# kossr.net
KiCad netlist of a schematic drawn in EAGLE
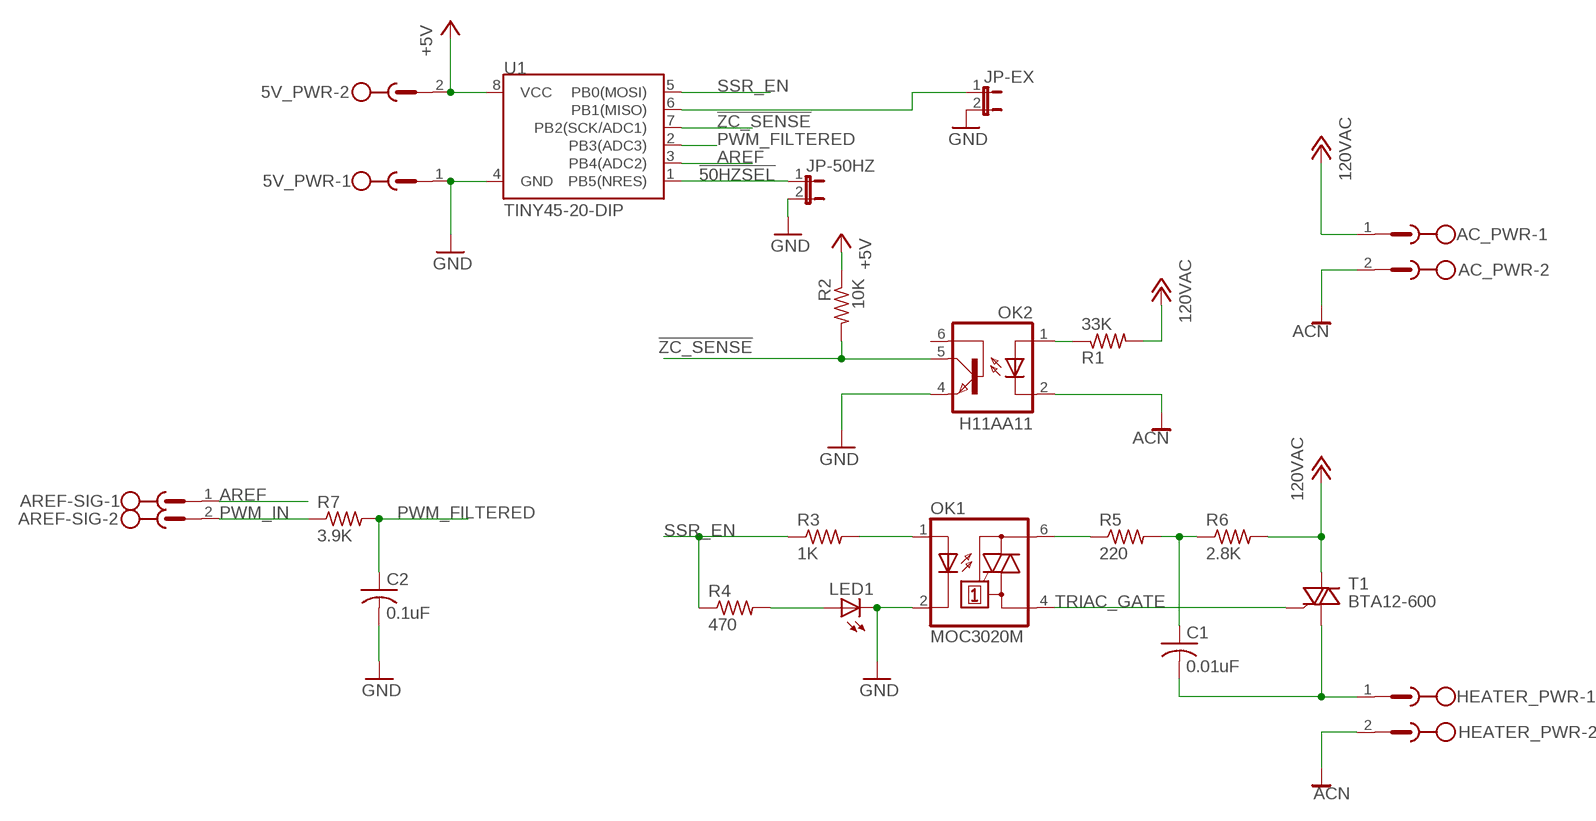
[diagram p0: schematic, sheet 1]

(export (version "E")
  (design (tool "Eeschema 10.0.6"))
  (components
    (comp (ref "5V_PWR")
      (value "MSTBV2")
      (footprint "eagle-import:MSTBV2")
      (libsource (lib "eagle-import") (part "MSTBV2"))
    )
    (comp (ref "AC_PWR")
      (value "MSTBV2")
      (footprint "eagle-import:MSTBV2")
      (libsource (lib "eagle-import") (part "MSTBV2"))
    )
    (comp (ref "AREF-SIG")
      (value "MSTBV2")
      (footprint "eagle-import:MSTBV2")
      (libsource (lib "eagle-import") (part "MSTBV2"))
    )
    (comp (ref "C1")
      (value "0.01uF")
      (footprint "eagle-import:C050-024X044")
      (libsource (lib "eagle-import") (part "C-US050-024X044"))
    )
    (comp (ref "C2")
      (value "0.1uF")
      (footprint "eagle-import:C025-024X044")
      (libsource (lib "eagle-import") (part "C-US025-024X044"))
    )
    (comp (ref "HEATER_PWR")
      (value "MSTBV2")
      (footprint "eagle-import:MSTBV2")
      (libsource (lib "eagle-import") (part "MSTBV2"))
    )
    (comp (ref "JP-50HZ")
      (value "JUMPER-2SMD-NO")
      (footprint "eagle-import:SJ_2S-NO")
      (libsource (lib "eagle-import") (part "JUMPER-2SMD-NO"))
    )
    (comp (ref "JP-EX")
      (value "JUMPER-2SMD-NO")
      (footprint "eagle-import:SJ_2S-NO")
      (libsource (lib "eagle-import") (part "JUMPER-2SMD-NO"))
    )
    (comp (ref "LED1")
      (value "LED3MM")
      (footprint "eagle-import:LED3MM")
      (libsource (lib "eagle-import") (part "LED3MM"))
    )
    (comp (ref "OK1")
      (value "MOC3020M")
      (footprint "eagle-import:DIL06")
      (fields (field (name "MF") "FAIRCHILD SEMICONDUCTOR") (field (name "MPN") "MOC3020-M"))
      (libsource (lib "eagle-import") (part "MOC30M20"))
    )
    (comp (ref "OK2")
      (value "H11AA11")
      (footprint "eagle-import:DIL06")
      (fields (field (name "MPN") "H11A1-M"))
      (libsource (lib "eagle-import") (part "H11AA11"))
    )
    (comp (ref "R1")
      (value "33K")
      (footprint "eagle-import:0207_7")
      (libsource (lib "eagle-import") (part "R-US_0207/7"))
    )
    (comp (ref "R2")
      (value "10K")
      (footprint "eagle-import:0207_7")
      (libsource (lib "eagle-import") (part "R-US_0207/7"))
    )
    (comp (ref "R3")
      (value "1K")
      (footprint "eagle-import:0207_7")
      (libsource (lib "eagle-import") (part "R-US_0207/7"))
    )
    (comp (ref "R4")
      (value "470")
      (footprint "eagle-import:0207_7")
      (libsource (lib "eagle-import") (part "R-US_0207/7"))
    )
    (comp (ref "R5")
      (value "220")
      (footprint "eagle-import:0207_7")
      (libsource (lib "eagle-import") (part "R-US_0207/7"))
    )
    (comp (ref "R6")
      (value "2.8K")
      (footprint "eagle-import:0207_7")
      (libsource (lib "eagle-import") (part "R-US_0207/7"))
    )
    (comp (ref "R7")
      (value "3.9K")
      (footprint "eagle-import:0207_7")
      (libsource (lib "eagle-import") (part "R-US_0207/7"))
    )
    (comp (ref "T1")
      (value "BTA12-600")
      (footprint "eagle-import:TO220AB")
      (libsource (lib "eagle-import") (part "BTA12-600"))
    )
    (comp (ref "U1")
      (value "TINY45-20-DIP")
      (footprint "eagle-import:DIP08")
      (libsource (lib "eagle-import") (part "ATTINY45TINY45-20-DIP"))
    )
  )
  (nets
    (net (code "1") (name "+5V") (class "Default")
      (node (ref "5V_PWR") (pin "2") (pinfunction "SK_2") (pintype "passive"))
      (node (ref "R2") (pin "1") (pinfunction "1_1") (pintype "passive"))
      (node (ref "U1") (pin "8") (pinfunction "VCC_8") (pintype "bidirectional"))
    )
    (net (code "2") (name "/AREF") (class "Default")
      (node (ref "AREF-SIG") (pin "1") (pinfunction "SK_1") (pintype "passive"))
      (node (ref "U1") (pin "3") (pinfunction "PB4(ADC2)_3") (pintype "bidirectional"))
    )
    (net (code "3") (name "/PWM_FILTERED") (class "Default")
      (node (ref "C2") (pin "1") (pinfunction "1_1") (pintype "passive"))
      (node (ref "R7") (pin "2") (pinfunction "2_2") (pintype "passive"))
      (node (ref "U1") (pin "2") (pinfunction "PB3(ADC3)_2") (pintype "bidirectional"))
    )
    (net (code "4") (name "/PWM_IN") (class "Default")
      (node (ref "AREF-SIG") (pin "2") (pinfunction "SK_2") (pintype "passive"))
      (node (ref "R7") (pin "1") (pinfunction "1_1") (pintype "passive"))
    )
    (net (code "5") (name "/SSR_EN") (class "Default")
      (node (ref "R3") (pin "1") (pinfunction "1_1") (pintype "passive"))
      (node (ref "R4") (pin "1") (pinfunction "1_1") (pintype "passive"))
      (node (ref "U1") (pin "5") (pinfunction "PB0(MOSI)_5") (pintype "bidirectional"))
    )
    (net (code "6") (name "/TRIAC_GATE") (class "Default")
      (node (ref "OK1") (pin "4") (pinfunction "A1_4") (pintype "passive"))
      (node (ref "T1") (pin "3") (pinfunction "G_3") (pintype "passive"))
    )
    (net (code "7") (name "/~{50HZSEL}") (class "Default")
      (node (ref "JP-50HZ") (pin "1") (pinfunction "1_1") (pintype "passive"))
      (node (ref "U1") (pin "1") (pinfunction "PB5(NRES)_1") (pintype "bidirectional"))
    )
    (net (code "8") (name "/~{ZC_SENSE}") (class "Default")
      (node (ref "OK2") (pin "5") (pinfunction "COL_5") (pintype "passive"))
      (node (ref "R2") (pin "2") (pinfunction "2_2") (pintype "passive"))
      (node (ref "U1") (pin "7") (pinfunction "PB2(SCK/ADC1)_7") (pintype "bidirectional"))
    )
    (net (code "9") (name "120VAC") (class "Default")
      (node (ref "AC_PWR") (pin "1") (pinfunction "SK_1") (pintype "passive"))
      (node (ref "R1") (pin "2") (pinfunction "2_2") (pintype "passive"))
      (node (ref "R6") (pin "2") (pinfunction "2_2") (pintype "passive"))
      (node (ref "T1") (pin "2") (pinfunction "A2_2") (pintype "passive"))
    )
    (net (code "10") (name "ACN") (class "Default")
      (node (ref "AC_PWR") (pin "2") (pinfunction "SK_2") (pintype "passive"))
      (node (ref "HEATER_PWR") (pin "2") (pinfunction "SK_2") (pintype "passive"))
      (node (ref "OK2") (pin "2") (pinfunction "C_2") (pintype "passive"))
    )
    (net (code "11") (name "GND") (class "Default")
      (node (ref "5V_PWR") (pin "1") (pinfunction "SK_1") (pintype "passive"))
      (node (ref "C2") (pin "2") (pinfunction "2_2") (pintype "passive"))
      (node (ref "JP-50HZ") (pin "2") (pinfunction "2_2") (pintype "passive"))
      (node (ref "JP-EX") (pin "2") (pinfunction "2_2") (pintype "passive"))
      (node (ref "LED1") (pin "K") (pinfunction "C_K") (pintype "passive"))
      (node (ref "OK1") (pin "2") (pinfunction "C_2") (pintype "passive"))
      (node (ref "OK2") (pin "4") (pinfunction "EMI_4") (pintype "passive"))
      (node (ref "U1") (pin "4") (pinfunction "GND_4") (pintype "bidirectional"))
    )
    (net (code "12") (name "Net-(C1-Pad1)") (class "Default")
      (node (ref "C1") (pin "1") (pinfunction "1_1") (pintype "passive"))
      (node (ref "R5") (pin "2") (pinfunction "2_2") (pintype "passive"))
      (node (ref "R6") (pin "1") (pinfunction "1_1") (pintype "passive"))
    )
    (net (code "13") (name "Net-(HEATER_PWRA-SK)") (class "Default")
      (node (ref "C1") (pin "2") (pinfunction "2_2") (pintype "passive"))
      (node (ref "HEATER_PWR") (pin "1") (pinfunction "SK_1") (pintype "passive"))
      (node (ref "T1") (pin "1") (pinfunction "A1_1") (pintype "passive"))
    )
    (net (code "14") (name "Net-(LED1-PadA)") (class "Default")
      (node (ref "LED1") (pin "A") (pinfunction "A_A") (pintype "passive"))
      (node (ref "R4") (pin "2") (pinfunction "2_2") (pintype "passive"))
    )
    (net (code "15") (name "Net-(OK1-A)") (class "Default")
      (node (ref "OK1") (pin "1") (pinfunction "A_1") (pintype "passive"))
      (node (ref "R3") (pin "2") (pinfunction "2_2") (pintype "passive"))
    )
    (net (code "16") (name "Net-(OK1-A2)") (class "Default")
      (node (ref "OK1") (pin "6") (pinfunction "A2_6") (pintype "passive"))
      (node (ref "R5") (pin "1") (pinfunction "1_1") (pintype "passive"))
    )
    (net (code "17") (name "Net-(OK2-A)") (class "Default")
      (node (ref "OK2") (pin "1") (pinfunction "A_1") (pintype "passive"))
      (node (ref "R1") (pin "1") (pinfunction "1_1") (pintype "passive"))
    )
    (net (code "18") (name "Net-(U1-PB1(MISO))") (class "Default")
      (node (ref "JP-EX") (pin "1") (pinfunction "1_1") (pintype "passive"))
      (node (ref "U1") (pin "6") (pinfunction "PB1(MISO)_6") (pintype "bidirectional"))
    )
    (net (code "19") (name "unconnected-(OK2-BAS-Pad6)") (class "Default")
      (node (ref "OK2") (pin "6") (pinfunction "BAS_6") (pintype "passive"))
    )
  )
)
